# MotorDriver.net
KiCad netlist of a schematic drawn in Altium Designer
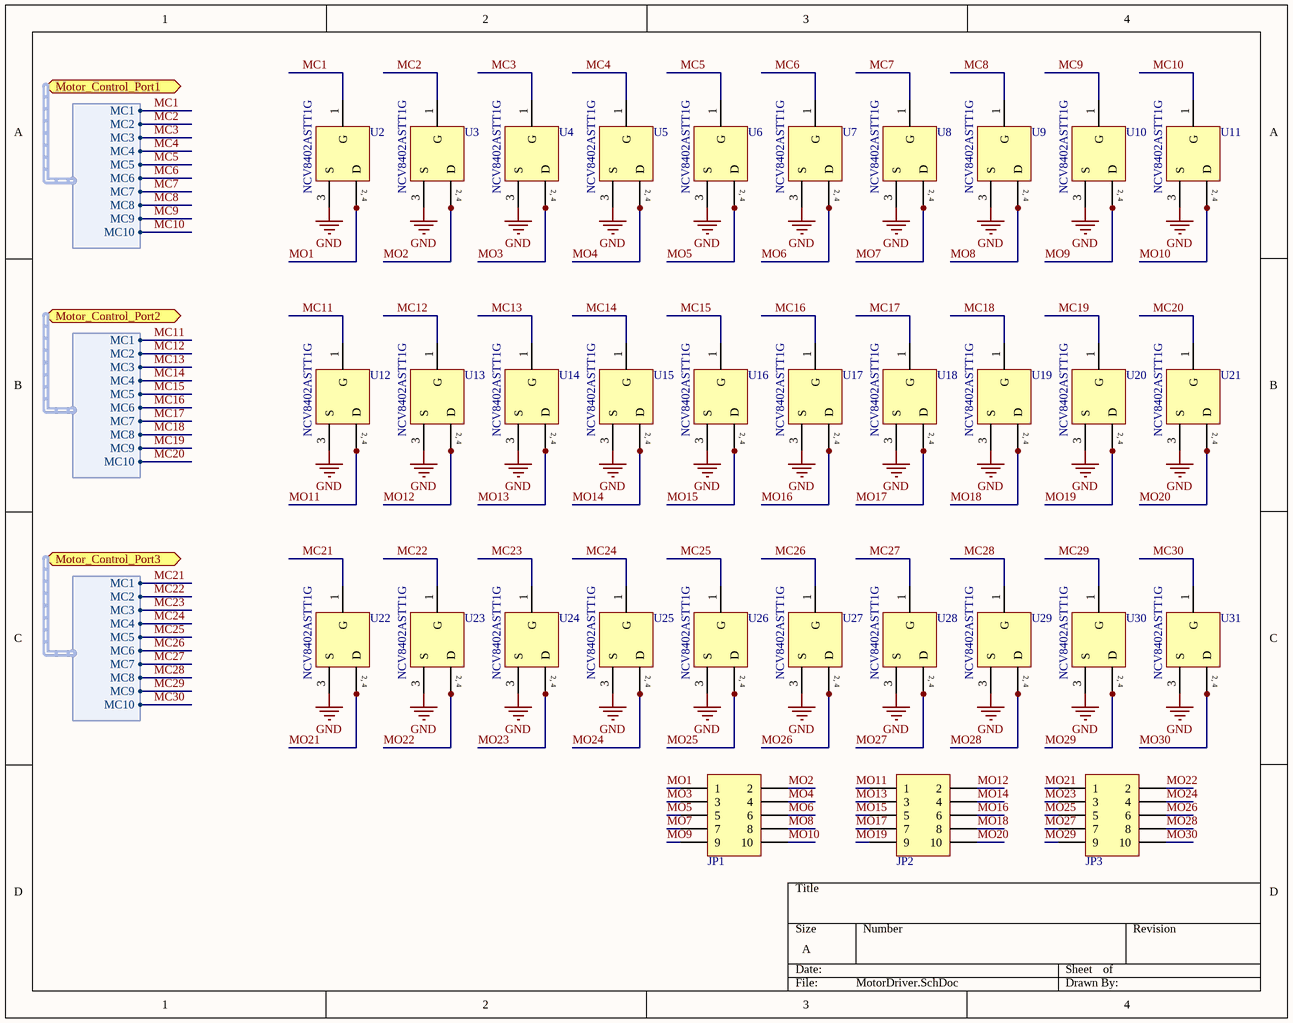
[diagram p0: MotorDriver.SchDoc]

(export (version "E")
  (design (tool "Eeschema 10.0.6"))
  (components
    (comp (ref "JP1")
      (value "Header 5x2 2.54mm")
      (footprint "2X5")
      (description "Header, 8-Pin")
      (libsource (lib "HSBNE-Vend") (part "Header 5x2"))
    )
    (comp (ref "JP2")
      (value "Header 5x2 2.54mm")
      (footprint "2X5")
      (description "Header, 8-Pin")
      (libsource (lib "HSBNE-Vend") (part "Header 5x2"))
    )
    (comp (ref "JP3")
      (value "Header 5x2 2.54mm")
      (footprint "2X5")
      (description "Header, 8-Pin")
      (libsource (lib "HSBNE-Vend") (part "Header 5x2"))
    )
    (comp (ref "U2")
      (value "NCV8402ASTT1G")
      (footprint "ONSC-SOT-223-4-318E-04_V")
      (fields (field (name "MANUFACTURER") "On Semiconductor"))
      (libsource (lib "Altium Content Vault") (part "ONSC-ProNMOS-G1S3D24_B-4"))
    )
    (comp (ref "U3")
      (value "NCV8402ASTT1G")
      (footprint "ONSC-SOT-223-4-318E-04_V")
      (fields (field (name "MANUFACTURER") "On Semiconductor"))
      (libsource (lib "Altium Content Vault") (part "ONSC-ProNMOS-G1S3D24_B-4"))
    )
    (comp (ref "U4")
      (value "NCV8402ASTT1G")
      (footprint "ONSC-SOT-223-4-318E-04_V")
      (fields (field (name "MANUFACTURER") "On Semiconductor"))
      (libsource (lib "Altium Content Vault") (part "ONSC-ProNMOS-G1S3D24_B-4"))
    )
    (comp (ref "U5")
      (value "NCV8402ASTT1G")
      (footprint "ONSC-SOT-223-4-318E-04_V")
      (fields (field (name "MANUFACTURER") "On Semiconductor"))
      (libsource (lib "Altium Content Vault") (part "ONSC-ProNMOS-G1S3D24_B-4"))
    )
    (comp (ref "U6")
      (value "NCV8402ASTT1G")
      (footprint "ONSC-SOT-223-4-318E-04_V")
      (fields (field (name "MANUFACTURER") "On Semiconductor"))
      (libsource (lib "Altium Content Vault") (part "ONSC-ProNMOS-G1S3D24_B-4"))
    )
    (comp (ref "U7")
      (value "NCV8402ASTT1G")
      (footprint "ONSC-SOT-223-4-318E-04_V")
      (fields (field (name "MANUFACTURER") "On Semiconductor"))
      (libsource (lib "Altium Content Vault") (part "ONSC-ProNMOS-G1S3D24_B-4"))
    )
    (comp (ref "U8")
      (value "NCV8402ASTT1G")
      (footprint "ONSC-SOT-223-4-318E-04_V")
      (fields (field (name "MANUFACTURER") "On Semiconductor"))
      (libsource (lib "Altium Content Vault") (part "ONSC-ProNMOS-G1S3D24_B-4"))
    )
    (comp (ref "U9")
      (value "NCV8402ASTT1G")
      (footprint "ONSC-SOT-223-4-318E-04_V")
      (fields (field (name "MANUFACTURER") "On Semiconductor"))
      (libsource (lib "Altium Content Vault") (part "ONSC-ProNMOS-G1S3D24_B-4"))
    )
    (comp (ref "U10")
      (value "NCV8402ASTT1G")
      (footprint "ONSC-SOT-223-4-318E-04_V")
      (fields (field (name "MANUFACTURER") "On Semiconductor"))
      (libsource (lib "Altium Content Vault") (part "ONSC-ProNMOS-G1S3D24_B-4"))
    )
    (comp (ref "U11")
      (value "NCV8402ASTT1G")
      (footprint "ONSC-SOT-223-4-318E-04_V")
      (fields (field (name "MANUFACTURER") "On Semiconductor"))
      (libsource (lib "Altium Content Vault") (part "ONSC-ProNMOS-G1S3D24_B-4"))
    )
    (comp (ref "U12")
      (value "NCV8402ASTT1G")
      (footprint "ONSC-SOT-223-4-318E-04_V")
      (fields (field (name "MANUFACTURER") "On Semiconductor"))
      (libsource (lib "Altium Content Vault") (part "ONSC-ProNMOS-G1S3D24_B-4"))
    )
    (comp (ref "U13")
      (value "NCV8402ASTT1G")
      (footprint "ONSC-SOT-223-4-318E-04_V")
      (fields (field (name "MANUFACTURER") "On Semiconductor"))
      (libsource (lib "Altium Content Vault") (part "ONSC-ProNMOS-G1S3D24_B-4"))
    )
    (comp (ref "U14")
      (value "NCV8402ASTT1G")
      (footprint "ONSC-SOT-223-4-318E-04_V")
      (fields (field (name "MANUFACTURER") "On Semiconductor"))
      (libsource (lib "Altium Content Vault") (part "ONSC-ProNMOS-G1S3D24_B-4"))
    )
    (comp (ref "U15")
      (value "NCV8402ASTT1G")
      (footprint "ONSC-SOT-223-4-318E-04_V")
      (fields (field (name "MANUFACTURER") "On Semiconductor"))
      (libsource (lib "Altium Content Vault") (part "ONSC-ProNMOS-G1S3D24_B-4"))
    )
    (comp (ref "U16")
      (value "NCV8402ASTT1G")
      (footprint "ONSC-SOT-223-4-318E-04_V")
      (fields (field (name "MANUFACTURER") "On Semiconductor"))
      (libsource (lib "Altium Content Vault") (part "ONSC-ProNMOS-G1S3D24_B-4"))
    )
    (comp (ref "U17")
      (value "NCV8402ASTT1G")
      (footprint "ONSC-SOT-223-4-318E-04_V")
      (fields (field (name "MANUFACTURER") "On Semiconductor"))
      (libsource (lib "Altium Content Vault") (part "ONSC-ProNMOS-G1S3D24_B-4"))
    )
    (comp (ref "U18")
      (value "NCV8402ASTT1G")
      (footprint "ONSC-SOT-223-4-318E-04_V")
      (fields (field (name "MANUFACTURER") "On Semiconductor"))
      (libsource (lib "Altium Content Vault") (part "ONSC-ProNMOS-G1S3D24_B-4"))
    )
    (comp (ref "U19")
      (value "NCV8402ASTT1G")
      (footprint "ONSC-SOT-223-4-318E-04_V")
      (fields (field (name "MANUFACTURER") "On Semiconductor"))
      (libsource (lib "Altium Content Vault") (part "ONSC-ProNMOS-G1S3D24_B-4"))
    )
    (comp (ref "U20")
      (value "NCV8402ASTT1G")
      (footprint "ONSC-SOT-223-4-318E-04_V")
      (fields (field (name "MANUFACTURER") "On Semiconductor"))
      (libsource (lib "Altium Content Vault") (part "ONSC-ProNMOS-G1S3D24_B-4"))
    )
    (comp (ref "U21")
      (value "NCV8402ASTT1G")
      (footprint "ONSC-SOT-223-4-318E-04_V")
      (fields (field (name "MANUFACTURER") "On Semiconductor"))
      (libsource (lib "Altium Content Vault") (part "ONSC-ProNMOS-G1S3D24_B-4"))
    )
    (comp (ref "U22")
      (value "NCV8402ASTT1G")
      (footprint "ONSC-SOT-223-4-318E-04_V")
      (fields (field (name "MANUFACTURER") "On Semiconductor"))
      (libsource (lib "Altium Content Vault") (part "ONSC-ProNMOS-G1S3D24_B-4"))
    )
    (comp (ref "U23")
      (value "NCV8402ASTT1G")
      (footprint "ONSC-SOT-223-4-318E-04_V")
      (fields (field (name "MANUFACTURER") "On Semiconductor"))
      (libsource (lib "Altium Content Vault") (part "ONSC-ProNMOS-G1S3D24_B-4"))
    )
    (comp (ref "U24")
      (value "NCV8402ASTT1G")
      (footprint "ONSC-SOT-223-4-318E-04_V")
      (fields (field (name "MANUFACTURER") "On Semiconductor"))
      (libsource (lib "Altium Content Vault") (part "ONSC-ProNMOS-G1S3D24_B-4"))
    )
    (comp (ref "U25")
      (value "NCV8402ASTT1G")
      (footprint "ONSC-SOT-223-4-318E-04_V")
      (fields (field (name "MANUFACTURER") "On Semiconductor"))
      (libsource (lib "Altium Content Vault") (part "ONSC-ProNMOS-G1S3D24_B-4"))
    )
    (comp (ref "U26")
      (value "NCV8402ASTT1G")
      (footprint "ONSC-SOT-223-4-318E-04_V")
      (fields (field (name "MANUFACTURER") "On Semiconductor"))
      (libsource (lib "Altium Content Vault") (part "ONSC-ProNMOS-G1S3D24_B-4"))
    )
    (comp (ref "U27")
      (value "NCV8402ASTT1G")
      (footprint "ONSC-SOT-223-4-318E-04_V")
      (fields (field (name "MANUFACTURER") "On Semiconductor"))
      (libsource (lib "Altium Content Vault") (part "ONSC-ProNMOS-G1S3D24_B-4"))
    )
    (comp (ref "U28")
      (value "NCV8402ASTT1G")
      (footprint "ONSC-SOT-223-4-318E-04_V")
      (fields (field (name "MANUFACTURER") "On Semiconductor"))
      (libsource (lib "Altium Content Vault") (part "ONSC-ProNMOS-G1S3D24_B-4"))
    )
    (comp (ref "U29")
      (value "NCV8402ASTT1G")
      (footprint "ONSC-SOT-223-4-318E-04_V")
      (fields (field (name "MANUFACTURER") "On Semiconductor"))
      (libsource (lib "Altium Content Vault") (part "ONSC-ProNMOS-G1S3D24_B-4"))
    )
    (comp (ref "U30")
      (value "NCV8402ASTT1G")
      (footprint "ONSC-SOT-223-4-318E-04_V")
      (fields (field (name "MANUFACTURER") "On Semiconductor"))
      (libsource (lib "Altium Content Vault") (part "ONSC-ProNMOS-G1S3D24_B-4"))
    )
    (comp (ref "U31")
      (value "NCV8402ASTT1G")
      (footprint "ONSC-SOT-223-4-318E-04_V")
      (fields (field (name "MANUFACTURER") "On Semiconductor"))
      (libsource (lib "Altium Content Vault") (part "ONSC-ProNMOS-G1S3D24_B-4"))
    )
  )
  (nets
    (net (code "2") (name "/MC1") (class "Default")
      (node (ref "U2") (pin "1") (pinfunction "G_1") (pintype "passive"))
    )
    (net (code "3") (name "/MC2") (class "Default")
      (node (ref "U3") (pin "1") (pinfunction "G_1") (pintype "passive"))
    )
    (net (code "4") (name "/MC3") (class "Default")
      (node (ref "U4") (pin "1") (pinfunction "G_1") (pintype "passive"))
    )
    (net (code "5") (name "/MC4") (class "Default")
      (node (ref "U5") (pin "1") (pinfunction "G_1") (pintype "passive"))
    )
    (net (code "6") (name "/MC5") (class "Default")
      (node (ref "U6") (pin "1") (pinfunction "G_1") (pintype "passive"))
    )
    (net (code "7") (name "/MC6") (class "Default")
      (node (ref "U7") (pin "1") (pinfunction "G_1") (pintype "passive"))
    )
    (net (code "8") (name "/MC7") (class "Default")
      (node (ref "U8") (pin "1") (pinfunction "G_1") (pintype "passive"))
    )
    (net (code "9") (name "/MC8") (class "Default")
      (node (ref "U9") (pin "1") (pinfunction "G_1") (pintype "passive"))
    )
    (net (code "10") (name "/MC9") (class "Default")
      (node (ref "U10") (pin "1") (pinfunction "G_1") (pintype "passive"))
    )
    (net (code "11") (name "/MC10") (class "Default")
      (node (ref "U11") (pin "1") (pinfunction "G_1") (pintype "passive"))
    )
    (net (code "12") (name "/MC11") (class "Default")
      (node (ref "U12") (pin "1") (pinfunction "G_1") (pintype "passive"))
    )
    (net (code "13") (name "/MC12") (class "Default")
      (node (ref "U13") (pin "1") (pinfunction "G_1") (pintype "passive"))
    )
    (net (code "14") (name "/MC13") (class "Default")
      (node (ref "U14") (pin "1") (pinfunction "G_1") (pintype "passive"))
    )
    (net (code "15") (name "/MC14") (class "Default")
      (node (ref "U15") (pin "1") (pinfunction "G_1") (pintype "passive"))
    )
    (net (code "16") (name "/MC15") (class "Default")
      (node (ref "U16") (pin "1") (pinfunction "G_1") (pintype "passive"))
    )
    (net (code "17") (name "/MC16") (class "Default")
      (node (ref "U17") (pin "1") (pinfunction "G_1") (pintype "passive"))
    )
    (net (code "18") (name "/MC17") (class "Default")
      (node (ref "U18") (pin "1") (pinfunction "G_1") (pintype "passive"))
    )
    (net (code "19") (name "/MC18") (class "Default")
      (node (ref "U19") (pin "1") (pinfunction "G_1") (pintype "passive"))
    )
    (net (code "20") (name "/MC19") (class "Default")
      (node (ref "U20") (pin "1") (pinfunction "G_1") (pintype "passive"))
    )
    (net (code "21") (name "/MC20") (class "Default")
      (node (ref "U21") (pin "1") (pinfunction "G_1") (pintype "passive"))
    )
    (net (code "22") (name "/MC21") (class "Default")
      (node (ref "U22") (pin "1") (pinfunction "G_1") (pintype "passive"))
    )
    (net (code "23") (name "/MC22") (class "Default")
      (node (ref "U23") (pin "1") (pinfunction "G_1") (pintype "passive"))
    )
    (net (code "24") (name "/MC23") (class "Default")
      (node (ref "U24") (pin "1") (pinfunction "G_1") (pintype "passive"))
    )
    (net (code "25") (name "/MC24") (class "Default")
      (node (ref "U25") (pin "1") (pinfunction "G_1") (pintype "passive"))
    )
    (net (code "26") (name "/MC25") (class "Default")
      (node (ref "U26") (pin "1") (pinfunction "G_1") (pintype "passive"))
    )
    (net (code "27") (name "/MC26") (class "Default")
      (node (ref "U27") (pin "1") (pinfunction "G_1") (pintype "passive"))
    )
    (net (code "28") (name "/MC27") (class "Default")
      (node (ref "U28") (pin "1") (pinfunction "G_1") (pintype "passive"))
    )
    (net (code "29") (name "/MC28") (class "Default")
      (node (ref "U29") (pin "1") (pinfunction "G_1") (pintype "passive"))
    )
    (net (code "30") (name "/MC29") (class "Default")
      (node (ref "U30") (pin "1") (pinfunction "G_1") (pintype "passive"))
    )
    (net (code "31") (name "/MC30") (class "Default")
      (node (ref "U31") (pin "1") (pinfunction "G_1") (pintype "passive"))
    )
    (net (code "32") (name "/MO1") (class "Default")
      (node (ref "JP1") (pin "1") (pinfunction "1_1") (pintype "passive"))
      (node (ref "U2") (pin "2") (pinfunction "D_2") (pintype "passive"))
      (node (ref "U2") (pin "4") (pinfunction "D_4") (pintype "passive"))
    )
    (net (code "33") (name "/MO2") (class "Default")
      (node (ref "JP1") (pin "2") (pinfunction "2_2") (pintype "passive"))
      (node (ref "U3") (pin "2") (pinfunction "D_2") (pintype "passive"))
      (node (ref "U3") (pin "4") (pinfunction "D_4") (pintype "passive"))
    )
    (net (code "34") (name "/MO3") (class "Default")
      (node (ref "JP1") (pin "3") (pinfunction "3_3") (pintype "passive"))
      (node (ref "U4") (pin "2") (pinfunction "D_2") (pintype "passive"))
      (node (ref "U4") (pin "4") (pinfunction "D_4") (pintype "passive"))
    )
    (net (code "35") (name "/MO4") (class "Default")
      (node (ref "JP1") (pin "4") (pinfunction "4_4") (pintype "passive"))
      (node (ref "U5") (pin "2") (pinfunction "D_2") (pintype "passive"))
      (node (ref "U5") (pin "4") (pinfunction "D_4") (pintype "passive"))
    )
    (net (code "36") (name "/MO5") (class "Default")
      (node (ref "JP1") (pin "5") (pinfunction "5_5") (pintype "passive"))
      (node (ref "U6") (pin "2") (pinfunction "D_2") (pintype "passive"))
      (node (ref "U6") (pin "4") (pinfunction "D_4") (pintype "passive"))
    )
    (net (code "37") (name "/MO6") (class "Default")
      (node (ref "JP1") (pin "6") (pinfunction "6_6") (pintype "passive"))
      (node (ref "U7") (pin "2") (pinfunction "D_2") (pintype "passive"))
      (node (ref "U7") (pin "4") (pinfunction "D_4") (pintype "passive"))
    )
    (net (code "38") (name "/MO7") (class "Default")
      (node (ref "JP1") (pin "7") (pinfunction "7_7") (pintype "passive"))
      (node (ref "U8") (pin "2") (pinfunction "D_2") (pintype "passive"))
      (node (ref "U8") (pin "4") (pinfunction "D_4") (pintype "passive"))
    )
    (net (code "39") (name "/MO8") (class "Default")
      (node (ref "JP1") (pin "8") (pinfunction "8_8") (pintype "passive"))
      (node (ref "U9") (pin "2") (pinfunction "D_2") (pintype "passive"))
      (node (ref "U9") (pin "4") (pinfunction "D_4") (pintype "passive"))
    )
    (net (code "40") (name "/MO9") (class "Default")
      (node (ref "JP1") (pin "9") (pinfunction "9_9") (pintype "passive"))
      (node (ref "U10") (pin "2") (pinfunction "D_2") (pintype "passive"))
      (node (ref "U10") (pin "4") (pinfunction "D_4") (pintype "passive"))
    )
    (net (code "41") (name "/MO10") (class "Default")
      (node (ref "JP1") (pin "10") (pinfunction "10_10") (pintype "passive"))
      (node (ref "U11") (pin "2") (pinfunction "D_2") (pintype "passive"))
      (node (ref "U11") (pin "4") (pinfunction "D_4") (pintype "passive"))
    )
    (net (code "42") (name "/MO11") (class "Default")
      (node (ref "JP2") (pin "1") (pinfunction "1_1") (pintype "passive"))
      (node (ref "U12") (pin "2") (pinfunction "D_2") (pintype "passive"))
      (node (ref "U12") (pin "4") (pinfunction "D_4") (pintype "passive"))
    )
    (net (code "43") (name "/MO12") (class "Default")
      (node (ref "JP2") (pin "2") (pinfunction "2_2") (pintype "passive"))
      (node (ref "U13") (pin "2") (pinfunction "D_2") (pintype "passive"))
      (node (ref "U13") (pin "4") (pinfunction "D_4") (pintype "passive"))
    )
    (net (code "44") (name "/MO13") (class "Default")
      (node (ref "JP2") (pin "3") (pinfunction "3_3") (pintype "passive"))
      (node (ref "U14") (pin "2") (pinfunction "D_2") (pintype "passive"))
      (node (ref "U14") (pin "4") (pinfunction "D_4") (pintype "passive"))
    )
    (net (code "45") (name "/MO14") (class "Default")
      (node (ref "JP2") (pin "4") (pinfunction "4_4") (pintype "passive"))
      (node (ref "U15") (pin "2") (pinfunction "D_2") (pintype "passive"))
      (node (ref "U15") (pin "4") (pinfunction "D_4") (pintype "passive"))
    )
    (net (code "46") (name "/MO15") (class "Default")
      (node (ref "JP2") (pin "5") (pinfunction "5_5") (pintype "passive"))
      (node (ref "U16") (pin "2") (pinfunction "D_2") (pintype "passive"))
      (node (ref "U16") (pin "4") (pinfunction "D_4") (pintype "passive"))
    )
    (net (code "47") (name "/MO16") (class "Default")
      (node (ref "JP2") (pin "6") (pinfunction "6_6") (pintype "passive"))
      (node (ref "U17") (pin "2") (pinfunction "D_2") (pintype "passive"))
      (node (ref "U17") (pin "4") (pinfunction "D_4") (pintype "passive"))
    )
    (net (code "48") (name "/MO17") (class "Default")
      (node (ref "JP2") (pin "7") (pinfunction "7_7") (pintype "passive"))
      (node (ref "U18") (pin "2") (pinfunction "D_2") (pintype "passive"))
      (node (ref "U18") (pin "4") (pinfunction "D_4") (pintype "passive"))
    )
    (net (code "49") (name "/MO18") (class "Default")
      (node (ref "JP2") (pin "8") (pinfunction "8_8") (pintype "passive"))
      (node (ref "U19") (pin "2") (pinfunction "D_2") (pintype "passive"))
      (node (ref "U19") (pin "4") (pinfunction "D_4") (pintype "passive"))
    )
    (net (code "50") (name "/MO19") (class "Default")
      (node (ref "JP2") (pin "9") (pinfunction "9_9") (pintype "passive"))
      (node (ref "U20") (pin "2") (pinfunction "D_2") (pintype "passive"))
      (node (ref "U20") (pin "4") (pinfunction "D_4") (pintype "passive"))
    )
    (net (code "51") (name "/MO20") (class "Default")
      (node (ref "JP2") (pin "10") (pinfunction "10_10") (pintype "passive"))
      (node (ref "U21") (pin "2") (pinfunction "D_2") (pintype "passive"))
      (node (ref "U21") (pin "4") (pinfunction "D_4") (pintype "passive"))
    )
    (net (code "52") (name "/MO21") (class "Default")
      (node (ref "JP3") (pin "1") (pinfunction "1_1") (pintype "passive"))
      (node (ref "U22") (pin "2") (pinfunction "D_2") (pintype "passive"))
      (node (ref "U22") (pin "4") (pinfunction "D_4") (pintype "passive"))
    )
    (net (code "53") (name "/MO22") (class "Default")
      (node (ref "JP3") (pin "2") (pinfunction "2_2") (pintype "passive"))
      (node (ref "U23") (pin "2") (pinfunction "D_2") (pintype "passive"))
      (node (ref "U23") (pin "4") (pinfunction "D_4") (pintype "passive"))
    )
    (net (code "54") (name "/MO23") (class "Default")
      (node (ref "JP3") (pin "3") (pinfunction "3_3") (pintype "passive"))
      (node (ref "U24") (pin "2") (pinfunction "D_2") (pintype "passive"))
      (node (ref "U24") (pin "4") (pinfunction "D_4") (pintype "passive"))
    )
    (net (code "55") (name "/MO24") (class "Default")
      (node (ref "JP3") (pin "4") (pinfunction "4_4") (pintype "passive"))
      (node (ref "U25") (pin "2") (pinfunction "D_2") (pintype "passive"))
      (node (ref "U25") (pin "4") (pinfunction "D_4") (pintype "passive"))
    )
    (net (code "56") (name "/MO25") (class "Default")
      (node (ref "JP3") (pin "5") (pinfunction "5_5") (pintype "passive"))
      (node (ref "U26") (pin "2") (pinfunction "D_2") (pintype "passive"))
      (node (ref "U26") (pin "4") (pinfunction "D_4") (pintype "passive"))
    )
    (net (code "57") (name "/MO26") (class "Default")
      (node (ref "JP3") (pin "6") (pinfunction "6_6") (pintype "passive"))
      (node (ref "U27") (pin "2") (pinfunction "D_2") (pintype "passive"))
      (node (ref "U27") (pin "4") (pinfunction "D_4") (pintype "passive"))
    )
    (net (code "58") (name "/MO27") (class "Default")
      (node (ref "JP3") (pin "7") (pinfunction "7_7") (pintype "passive"))
      (node (ref "U28") (pin "2") (pinfunction "D_2") (pintype "passive"))
      (node (ref "U28") (pin "4") (pinfunction "D_4") (pintype "passive"))
    )
    (net (code "59") (name "/MO28") (class "Default")
      (node (ref "JP3") (pin "8") (pinfunction "8_8") (pintype "passive"))
      (node (ref "U29") (pin "2") (pinfunction "D_2") (pintype "passive"))
      (node (ref "U29") (pin "4") (pinfunction "D_4") (pintype "passive"))
    )
    (net (code "60") (name "/MO29") (class "Default")
      (node (ref "JP3") (pin "9") (pinfunction "9_9") (pintype "passive"))
      (node (ref "U30") (pin "2") (pinfunction "D_2") (pintype "passive"))
      (node (ref "U30") (pin "4") (pinfunction "D_4") (pintype "passive"))
    )
    (net (code "61") (name "/MO30") (class "Default")
      (node (ref "JP3") (pin "10") (pinfunction "10_10") (pintype "passive"))
      (node (ref "U31") (pin "2") (pinfunction "D_2") (pintype "passive"))
      (node (ref "U31") (pin "4") (pinfunction "D_4") (pintype "passive"))
    )
    (net (code "63") (name "GND") (class "Default")
      (node (ref "U10") (pin "3") (pinfunction "S_3") (pintype "passive"))
      (node (ref "U11") (pin "3") (pinfunction "S_3") (pintype "passive"))
      (node (ref "U12") (pin "3") (pinfunction "S_3") (pintype "passive"))
      (node (ref "U13") (pin "3") (pinfunction "S_3") (pintype "passive"))
      (node (ref "U14") (pin "3") (pinfunction "S_3") (pintype "passive"))
      (node (ref "U15") (pin "3") (pinfunction "S_3") (pintype "passive"))
      (node (ref "U16") (pin "3") (pinfunction "S_3") (pintype "passive"))
      (node (ref "U17") (pin "3") (pinfunction "S_3") (pintype "passive"))
      (node (ref "U18") (pin "3") (pinfunction "S_3") (pintype "passive"))
      (node (ref "U19") (pin "3") (pinfunction "S_3") (pintype "passive"))
      (node (ref "U2") (pin "3") (pinfunction "S_3") (pintype "passive"))
      (node (ref "U20") (pin "3") (pinfunction "S_3") (pintype "passive"))
      (node (ref "U21") (pin "3") (pinfunction "S_3") (pintype "passive"))
      (node (ref "U22") (pin "3") (pinfunction "S_3") (pintype "passive"))
      (node (ref "U23") (pin "3") (pinfunction "S_3") (pintype "passive"))
      (node (ref "U24") (pin "3") (pinfunction "S_3") (pintype "passive"))
      (node (ref "U25") (pin "3") (pinfunction "S_3") (pintype "passive"))
      (node (ref "U26") (pin "3") (pinfunction "S_3") (pintype "passive"))
      (node (ref "U27") (pin "3") (pinfunction "S_3") (pintype "passive"))
      (node (ref "U28") (pin "3") (pinfunction "S_3") (pintype "passive"))
      (node (ref "U29") (pin "3") (pinfunction "S_3") (pintype "passive"))
      (node (ref "U3") (pin "3") (pinfunction "S_3") (pintype "passive"))
      (node (ref "U30") (pin "3") (pinfunction "S_3") (pintype "passive"))
      (node (ref "U31") (pin "3") (pinfunction "S_3") (pintype "passive"))
      (node (ref "U4") (pin "3") (pinfunction "S_3") (pintype "passive"))
      (node (ref "U5") (pin "3") (pinfunction "S_3") (pintype "passive"))
      (node (ref "U6") (pin "3") (pinfunction "S_3") (pintype "passive"))
      (node (ref "U7") (pin "3") (pinfunction "S_3") (pintype "passive"))
      (node (ref "U8") (pin "3") (pinfunction "S_3") (pintype "passive"))
      (node (ref "U9") (pin "3") (pinfunction "S_3") (pintype "passive"))
    )
  )
)
